# untitled.net
KiCad netlist of a schematic drawn in EAGLE
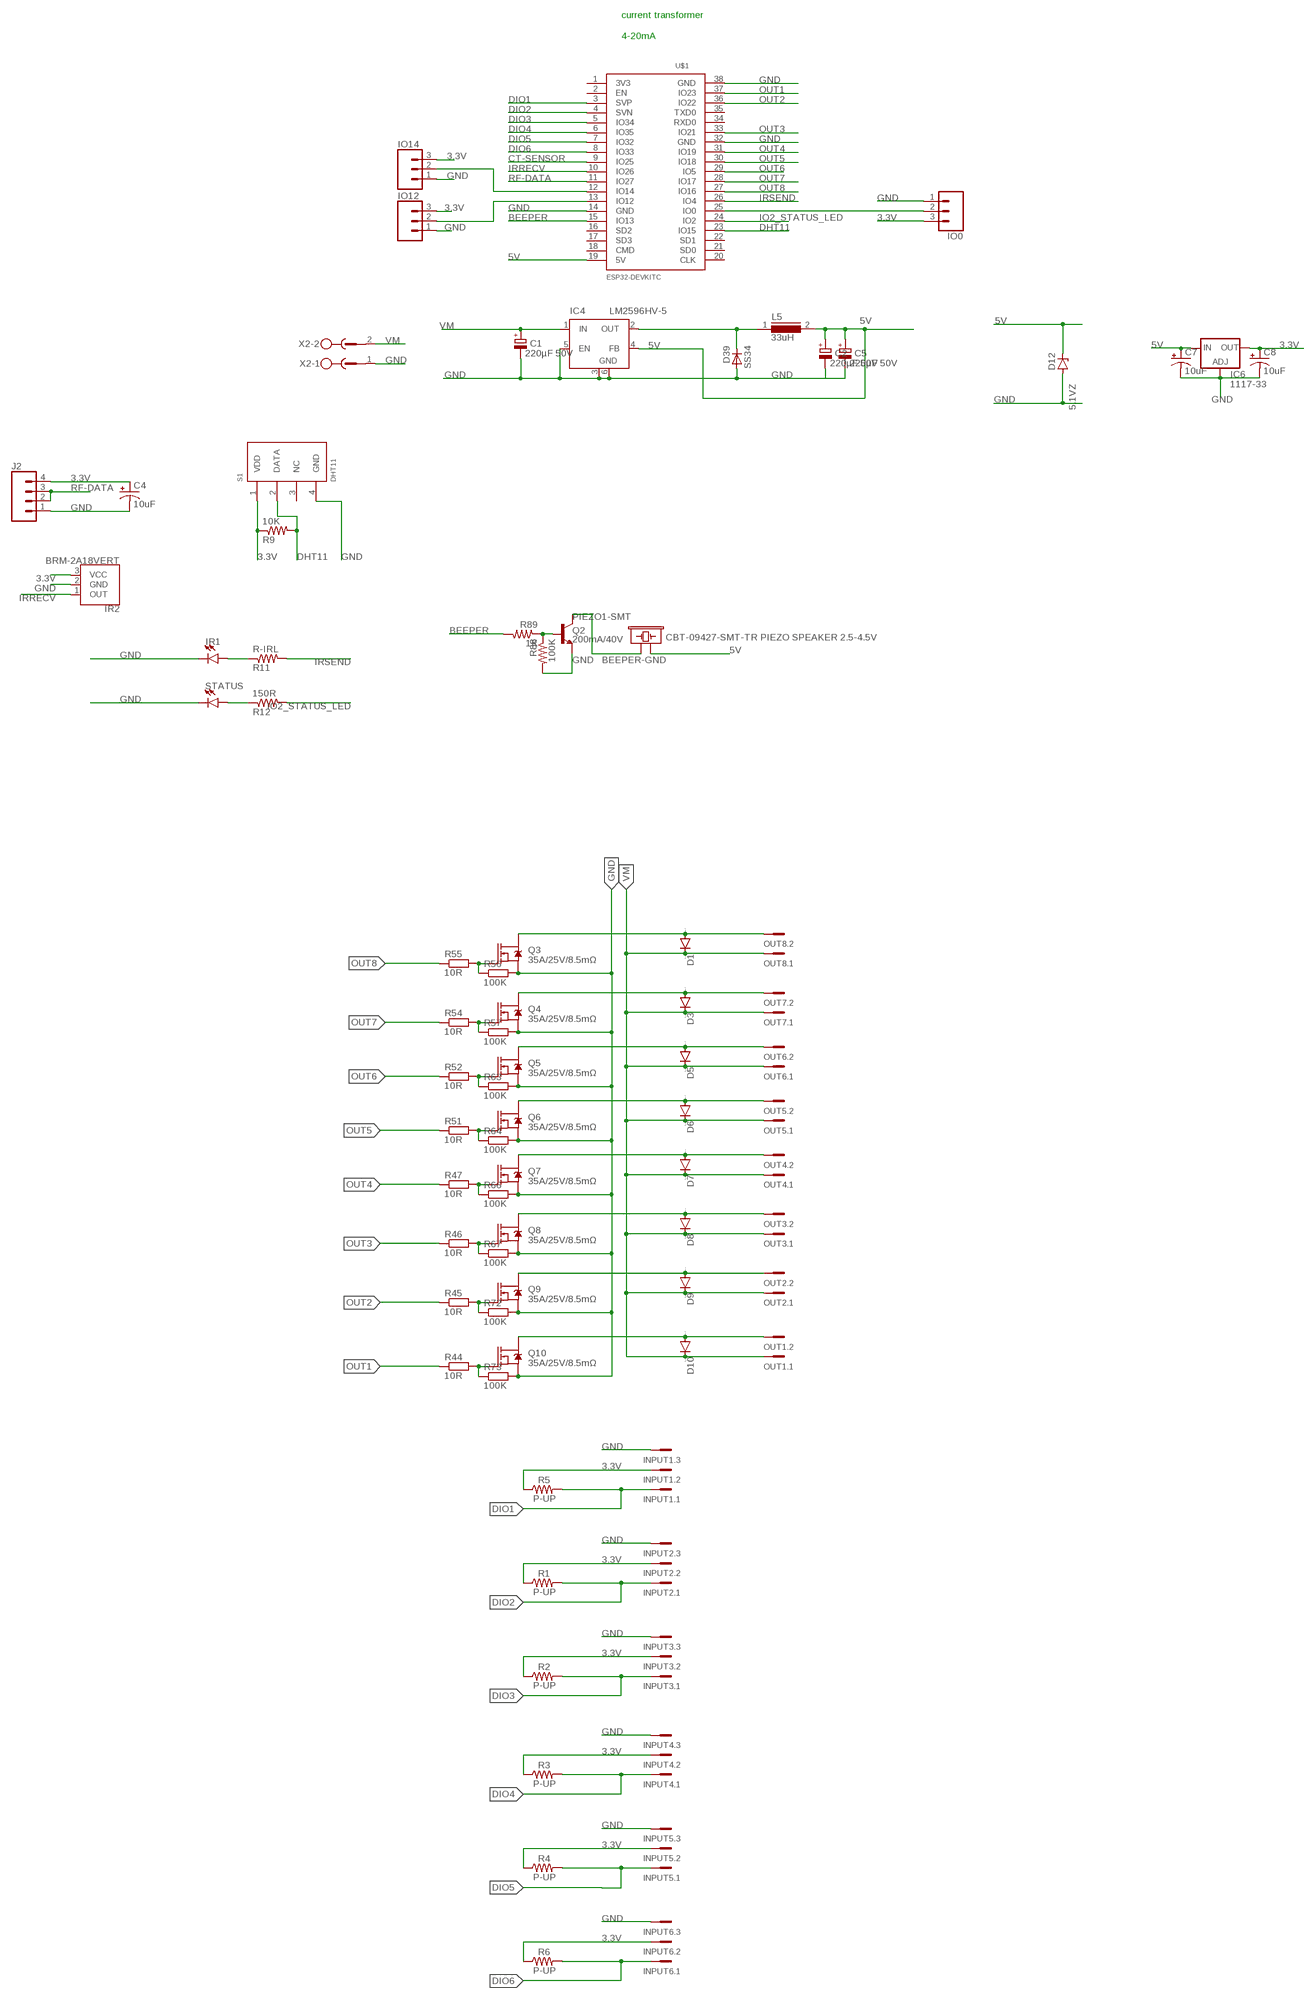
[diagram p0: schematic, sheet 1]

(export (version "E")
  (design (tool "Eeschema 10.0.6"))
  (components
    (comp (ref "C1")
      (value "220µF 50V")
      (footprint "eagle-import:E3,5-8")
      (libsource (lib "eagle-import") (part "CPOL-EUE3.5-8"))
    )
    (comp (ref "C2")
      (value "220µF 50V")
      (footprint "eagle-import:E3,5-8")
      (libsource (lib "eagle-import") (part "CPOL-EUE3.5-8"))
    )
    (comp (ref "C4")
      (value "10uF")
      (footprint "eagle-import:CPOL-RADIAL-10UF-25V")
      (libsource (lib "eagle-import") (part "CAP_POLPTH2"))
    )
    (comp (ref "C5")
      (value "220µF 50V")
      (footprint "eagle-import:E3,5-8")
      (libsource (lib "eagle-import") (part "CPOL-EUE3.5-8"))
    )
    (comp (ref "C7")
      (value "10uF")
      (footprint "eagle-import:CPOL-RADIAL-10UF-25V")
      (libsource (lib "eagle-import") (part "CAP_POLPTH2"))
    )
    (comp (ref "C8")
      (value "10uF")
      (footprint "eagle-import:CPOL-RADIAL-10UF-25V")
      (libsource (lib "eagle-import") (part "CAP_POLPTH2"))
    )
    (comp (ref "D1")
      (value "1N4148DO35-7")
      (footprint "eagle-import:DO35-7")
      (libsource (lib "eagle-import") (part "1N4148DO35-7"))
    )
    (comp (ref "D3")
      (value "1N4148DO35-7")
      (footprint "eagle-import:DO35-7")
      (libsource (lib "eagle-import") (part "1N4148DO35-7"))
    )
    (comp (ref "D5")
      (value "1N4148DO35-7")
      (footprint "eagle-import:DO35-7")
      (libsource (lib "eagle-import") (part "1N4148DO35-7"))
    )
    (comp (ref "D6")
      (value "1N4148DO35-7")
      (footprint "eagle-import:DO35-7")
      (libsource (lib "eagle-import") (part "1N4148DO35-7"))
    )
    (comp (ref "D7")
      (value "1N4148DO35-7")
      (footprint "eagle-import:DO35-7")
      (libsource (lib "eagle-import") (part "1N4148DO35-7"))
    )
    (comp (ref "D8")
      (value "1N4148DO35-7")
      (footprint "eagle-import:DO35-7")
      (libsource (lib "eagle-import") (part "1N4148DO35-7"))
    )
    (comp (ref "D9")
      (value "1N4148DO35-7")
      (footprint "eagle-import:DO35-7")
      (libsource (lib "eagle-import") (part "1N4148DO35-7"))
    )
    (comp (ref "D10")
      (value "1N4148DO35-7")
      (footprint "eagle-import:DO35-7")
      (libsource (lib "eagle-import") (part "1N4148DO35-7"))
    )
    (comp (ref "D12")
      (value "5.1VZ")
      (footprint "eagle-import:SMB")
      (libsource (lib "eagle-import") (part "ZENER-DIODESMB"))
    )
    (comp (ref "D39")
      (value "SS34")
      (footprint "eagle-import:SOD87")
      (libsource (lib "eagle-import") (part "D-SOD-87"))
    )
    (comp (ref "IC4")
      (value "LM2596HV-5")
      (footprint "eagle-import:TO263-5")
      (libsource (lib "eagle-import") (part "LM2596S"))
    )
    (comp (ref "IC6")
      (value "1117-33")
      (footprint "eagle-import:SOT223")
      (libsource (lib "eagle-import") (part "LD117A?S33TR"))
    )
    (comp (ref "INPUT1")
      (value "MCV3")
      (footprint "eagle-import:MCV3")
      (libsource (lib "eagle-import") (part "MCV3"))
    )
    (comp (ref "INPUT2")
      (value "MCV3")
      (footprint "eagle-import:MCV3")
      (libsource (lib "eagle-import") (part "MCV3"))
    )
    (comp (ref "INPUT3")
      (value "MCV3")
      (footprint "eagle-import:MCV3")
      (libsource (lib "eagle-import") (part "MCV3"))
    )
    (comp (ref "INPUT4")
      (value "MCV3")
      (footprint "eagle-import:MCV3")
      (libsource (lib "eagle-import") (part "MCV3"))
    )
    (comp (ref "INPUT5")
      (value "MCV3")
      (footprint "eagle-import:MCV3")
      (libsource (lib "eagle-import") (part "MCV3"))
    )
    (comp (ref "INPUT6")
      (value "MCV3")
      (footprint "eagle-import:MCV3")
      (libsource (lib "eagle-import") (part "MCV3"))
    )
    (comp (ref "IO0")
      (value "CONN_03LOCK")
      (footprint "eagle-import:1X03_LOCK")
      (libsource (lib "eagle-import") (part "CONN_03LOCK"))
    )
    (comp (ref "IO12")
      (value "CONN_03LOCK")
      (footprint "eagle-import:1X03_LOCK")
      (libsource (lib "eagle-import") (part "CONN_03LOCK"))
    )
    (comp (ref "IO14")
      (value "CONN_03LOCK")
      (footprint "eagle-import:1X03_LOCK")
      (libsource (lib "eagle-import") (part "CONN_03LOCK"))
    )
    (comp (ref "IR1")
      (value "LED3MM")
      (footprint "eagle-import:LED_3MM")
      (libsource (lib "eagle-import") (part "LED3MM"))
    )
    (comp (ref "IR2")
      (value "BRM-2A18VERT")
      (footprint "eagle-import:BRM-2508_VERT")
      (libsource (lib "eagle-import") (part "BRM-2A18VERT"))
    )
    (comp (ref "J2")
      (value "CONN_04LOCK")
      (footprint "eagle-import:1X04_LOCK")
      (libsource (lib "eagle-import") (part "CONN_04LOCK"))
    )
    (comp (ref "L5")
      (value "33uH")
      (footprint "eagle-import:DR127")
      (libsource (lib "eagle-import") (part "DR127"))
    )
    (comp (ref "OUT1")
      (value "MCV2")
      (footprint "eagle-import:MCV2")
      (libsource (lib "eagle-import") (part "MCV2"))
    )
    (comp (ref "OUT2")
      (value "MCV2")
      (footprint "eagle-import:MCV2")
      (libsource (lib "eagle-import") (part "MCV2"))
    )
    (comp (ref "OUT3")
      (value "MCV2")
      (footprint "eagle-import:MCV2")
      (libsource (lib "eagle-import") (part "MCV2"))
    )
    (comp (ref "OUT4")
      (value "MCV2")
      (footprint "eagle-import:MCV2")
      (libsource (lib "eagle-import") (part "MCV2"))
    )
    (comp (ref "OUT5")
      (value "MCV2")
      (footprint "eagle-import:MCV2")
      (libsource (lib "eagle-import") (part "MCV2"))
    )
    (comp (ref "OUT6")
      (value "MCV2")
      (footprint "eagle-import:MCV2")
      (libsource (lib "eagle-import") (part "MCV2"))
    )
    (comp (ref "OUT7")
      (value "MCV2")
      (footprint "eagle-import:MCV2")
      (libsource (lib "eagle-import") (part "MCV2"))
    )
    (comp (ref "OUT8")
      (value "MCV2")
      (footprint "eagle-import:MCV2")
      (libsource (lib "eagle-import") (part "MCV2"))
    )
    (comp (ref "PIEZO1-SMT")
      (value "CBT-09427-SMT-TR PIEZO SPEAKER 2.5-4.5V")
      (footprint "eagle-import:BUZZER-12MM")
      (libsource (lib "eagle-import") (part "BUZZER-PTH"))
    )
    (comp (ref "Q2")
      (value "200mA/40V")
      (footprint "eagle-import:TO-92")
      (libsource (lib "eagle-import") (part "TRANS_NPN-2N3904"))
    )
    (comp (ref "Q3")
      (value "35A/25V/8.5mΩ")
      (footprint "eagle-import:DPAK")
      (libsource (lib "eagle-import") (part "MOSFET-NCH-FDD8780"))
    )
    (comp (ref "Q4")
      (value "35A/25V/8.5mΩ")
      (footprint "eagle-import:DPAK")
      (libsource (lib "eagle-import") (part "MOSFET-NCH-FDD8780"))
    )
    (comp (ref "Q5")
      (value "35A/25V/8.5mΩ")
      (footprint "eagle-import:DPAK")
      (libsource (lib "eagle-import") (part "MOSFET-NCH-FDD8780"))
    )
    (comp (ref "Q6")
      (value "35A/25V/8.5mΩ")
      (footprint "eagle-import:DPAK")
      (libsource (lib "eagle-import") (part "MOSFET-NCH-FDD8780"))
    )
    (comp (ref "Q7")
      (value "35A/25V/8.5mΩ")
      (footprint "eagle-import:DPAK")
      (libsource (lib "eagle-import") (part "MOSFET-NCH-FDD8780"))
    )
    (comp (ref "Q8")
      (value "35A/25V/8.5mΩ")
      (footprint "eagle-import:DPAK")
      (libsource (lib "eagle-import") (part "MOSFET-NCH-FDD8780"))
    )
    (comp (ref "Q9")
      (value "35A/25V/8.5mΩ")
      (footprint "eagle-import:DPAK")
      (libsource (lib "eagle-import") (part "MOSFET-NCH-FDD8780"))
    )
    (comp (ref "Q10")
      (value "35A/25V/8.5mΩ")
      (footprint "eagle-import:DPAK")
      (libsource (lib "eagle-import") (part "MOSFET-NCH-FDD8780"))
    )
    (comp (ref "R1")
      (value "P-UP")
      (footprint "eagle-import:0204_7")
      (libsource (lib "eagle-import") (part "resistor_R-US_0204/7"))
    )
    (comp (ref "R2")
      (value "P-UP")
      (footprint "eagle-import:0204_7")
      (libsource (lib "eagle-import") (part "resistor_R-US_0204/7"))
    )
    (comp (ref "R3")
      (value "P-UP")
      (footprint "eagle-import:0204_7")
      (libsource (lib "eagle-import") (part "resistor_R-US_0204/7"))
    )
    (comp (ref "R4")
      (value "P-UP")
      (footprint "eagle-import:0204_7")
      (libsource (lib "eagle-import") (part "resistor_R-US_0204/7"))
    )
    (comp (ref "R5")
      (value "P-UP")
      (footprint "eagle-import:0204_7")
      (libsource (lib "eagle-import") (part "resistor_R-US_0204/7"))
    )
    (comp (ref "R6")
      (value "P-UP")
      (footprint "eagle-import:0204_7")
      (libsource (lib "eagle-import") (part "resistor_R-US_0204/7"))
    )
    (comp (ref "R9")
      (value "10K")
      (footprint "eagle-import:0204_7")
      (libsource (lib "eagle-import") (part "R-US_0204/7"))
    )
    (comp (ref "R11")
      (value "R-IRL")
      (footprint "eagle-import:0204_7")
      (libsource (lib "eagle-import") (part "R-US_0204/7"))
    )
    (comp (ref "R12")
      (value "150R")
      (footprint "eagle-import:0204_7")
      (libsource (lib "eagle-import") (part "R-US_0204/7"))
    )
    (comp (ref "R44")
      (value "10R")
      (footprint "eagle-import:0204_7")
      (libsource (lib "eagle-import") (part "R-EU_0204/7"))
    )
    (comp (ref "R45")
      (value "10R")
      (footprint "eagle-import:0204_7")
      (libsource (lib "eagle-import") (part "R-EU_0204/7"))
    )
    (comp (ref "R46")
      (value "10R")
      (footprint "eagle-import:0204_7")
      (libsource (lib "eagle-import") (part "R-EU_0204/7"))
    )
    (comp (ref "R47")
      (value "10R")
      (footprint "eagle-import:0204_7")
      (libsource (lib "eagle-import") (part "R-EU_0204/7"))
    )
    (comp (ref "R51")
      (value "10R")
      (footprint "eagle-import:0204_7")
      (libsource (lib "eagle-import") (part "R-EU_0204/7"))
    )
    (comp (ref "R52")
      (value "10R")
      (footprint "eagle-import:0204_7")
      (libsource (lib "eagle-import") (part "R-EU_0204/7"))
    )
    (comp (ref "R54")
      (value "10R")
      (footprint "eagle-import:0204_7")
      (libsource (lib "eagle-import") (part "R-EU_0204/7"))
    )
    (comp (ref "R55")
      (value "10R")
      (footprint "eagle-import:0204_7")
      (libsource (lib "eagle-import") (part "R-EU_0204/7"))
    )
    (comp (ref "R56")
      (value "100K")
      (footprint "eagle-import:0204_7")
      (libsource (lib "eagle-import") (part "R-EU_0204/7"))
    )
    (comp (ref "R57")
      (value "100K")
      (footprint "eagle-import:0204_7")
      (libsource (lib "eagle-import") (part "R-EU_0204/7"))
    )
    (comp (ref "R63")
      (value "100K")
      (footprint "eagle-import:0204_7")
      (libsource (lib "eagle-import") (part "R-EU_0204/7"))
    )
    (comp (ref "R64")
      (value "100K")
      (footprint "eagle-import:0204_7")
      (libsource (lib "eagle-import") (part "R-EU_0204/7"))
    )
    (comp (ref "R66")
      (value "100K")
      (footprint "eagle-import:0204_7")
      (libsource (lib "eagle-import") (part "R-EU_0204/7"))
    )
    (comp (ref "R67")
      (value "100K")
      (footprint "eagle-import:0204_7")
      (libsource (lib "eagle-import") (part "R-EU_0204/7"))
    )
    (comp (ref "R72")
      (value "100K")
      (footprint "eagle-import:0204_7")
      (libsource (lib "eagle-import") (part "R-EU_0204/7"))
    )
    (comp (ref "R73")
      (value "100K")
      (footprint "eagle-import:0204_7")
      (libsource (lib "eagle-import") (part "R-EU_0204/7"))
    )
    (comp (ref "R88")
      (value "100K")
      (footprint "eagle-import:0204_7")
      (libsource (lib "eagle-import") (part "adafruit_420_R-US_0204/7"))
    )
    (comp (ref "R89")
      (value "1K")
      (footprint "eagle-import:0204_7")
      (libsource (lib "eagle-import") (part "adafruit_420_R-US_0204/7"))
    )
    (comp (ref "S1")
      (value "DHT11")
      (footprint "eagle-import:DHT11")
      (libsource (lib "eagle-import") (part "DHT11"))
    )
    (comp (ref "STATUS")
      (value "LED3MM")
      (footprint "eagle-import:LED_3MM")
      (libsource (lib "eagle-import") (part "LED3MM"))
    )
    (comp (ref "U$1")
      (value "ESP32NODEMCU")
      (footprint "eagle-import:ESP32NODEMCU")
      (libsource (lib "eagle-import") (part "ESP32NODEMCU"))
    )
    (comp (ref "X2")
      (value "MSTBV2")
      (footprint "eagle-import:MSTBV2")
      (libsource (lib "eagle-import") (part "MSTBV2"))
    )
  )
  (nets
    (net (code "1") (name "/3.3V") (class "Default")
      (node (ref "C4") (pin "1") (pinfunction "+_1") (pintype "passive"))
      (node (ref "C8") (pin "1") (pinfunction "+_1") (pintype "passive"))
      (node (ref "IC6") (pin "4") (pinfunction "OUT_4") (pintype "passive"))
      (node (ref "INPUT1") (pin "2") (pinfunction "SK_2") (pintype "passive"))
      (node (ref "INPUT2") (pin "2") (pinfunction "SK_2") (pintype "passive"))
      (node (ref "INPUT3") (pin "2") (pinfunction "SK_2") (pintype "passive"))
      (node (ref "INPUT4") (pin "2") (pinfunction "SK_2") (pintype "passive"))
      (node (ref "INPUT5") (pin "2") (pinfunction "SK_2") (pintype "passive"))
      (node (ref "INPUT6") (pin "2") (pinfunction "SK_2") (pintype "passive"))
      (node (ref "IO0") (pin "3") (pinfunction "3_3") (pintype "passive"))
      (node (ref "IO12") (pin "3") (pinfunction "3_3") (pintype "passive"))
      (node (ref "IO14") (pin "3") (pinfunction "3_3") (pintype "passive"))
      (node (ref "IR2") (pin "3") (pinfunction "VCC_3") (pintype "bidirectional"))
      (node (ref "J2") (pin "4") (pinfunction "4_4") (pintype "passive"))
      (node (ref "R1") (pin "1") (pinfunction "1_1") (pintype "passive"))
      (node (ref "R2") (pin "1") (pinfunction "1_1") (pintype "passive"))
      (node (ref "R3") (pin "1") (pinfunction "1_1") (pintype "passive"))
      (node (ref "R4") (pin "1") (pinfunction "1_1") (pintype "passive"))
      (node (ref "R5") (pin "1") (pinfunction "1_1") (pintype "passive"))
      (node (ref "R6") (pin "1") (pinfunction "1_1") (pintype "passive"))
      (node (ref "R9") (pin "1") (pinfunction "1_1") (pintype "passive"))
      (node (ref "S1") (pin "1") (pinfunction "VDD_1") (pintype "power_in"))
    )
    (net (code "2") (name "/5V") (class "Default")
      (node (ref "C2") (pin "+") (pinfunction "+_+") (pintype "passive"))
      (node (ref "C5") (pin "+") (pinfunction "+_+") (pintype "passive"))
      (node (ref "C7") (pin "1") (pinfunction "+_1") (pintype "passive"))
      (node (ref "D12") (pin "C") (pinfunction "C_C") (pintype "passive"))
      (node (ref "IC4") (pin "4") (pinfunction "FB_4") (pintype "input"))
      (node (ref "IC6") (pin "3") (pinfunction "IN_3") (pintype "input"))
      (node (ref "L5") (pin "2") (pinfunction "2_2") (pintype "passive"))
      (node (ref "PIEZO1-SMT") (pin "+") (pinfunction "1_+") (pintype "passive"))
      (node (ref "U$1") (pin "19") (pinfunction "5V_19") (pintype "bidirectional"))
    )
    (net (code "3") (name "/BEEPER") (class "Default")
      (node (ref "R89") (pin "2") (pinfunction "2_2") (pintype "passive"))
      (node (ref "U$1") (pin "15") (pinfunction "IO13_15") (pintype "bidirectional"))
    )
    (net (code "4") (name "/BEEPER-GND") (class "Default")
      (node (ref "PIEZO1-SMT") (pin "-") (pinfunction "2_-") (pintype "passive"))
      (node (ref "Q2") (pin "3") (pinfunction "C_3") (pintype "passive"))
    )
    (net (code "5") (name "/CT-SENSOR") (class "Default")
      (node (ref "U$1") (pin "9") (pinfunction "IO25_9") (pintype "bidirectional"))
    )
    (net (code "6") (name "/DHT11") (class "Default")
      (node (ref "R9") (pin "2") (pinfunction "2_2") (pintype "passive"))
      (node (ref "S1") (pin "2") (pinfunction "DATA_2") (pintype "bidirectional"))
      (node (ref "U$1") (pin "23") (pinfunction "IO15_23") (pintype "bidirectional"))
    )
    (net (code "7") (name "/IO2_STATUS_LED") (class "Default")
      (node (ref "R12") (pin "2") (pinfunction "2_2") (pintype "passive"))
      (node (ref "U$1") (pin "24") (pinfunction "IO2_24") (pintype "bidirectional"))
    )
    (net (code "8") (name "/IRRECV") (class "Default")
      (node (ref "IR2") (pin "1") (pinfunction "OUT_1") (pintype "bidirectional"))
      (node (ref "U$1") (pin "10") (pinfunction "IO26_10") (pintype "bidirectional"))
    )
    (net (code "9") (name "/IRSEND") (class "Default")
      (node (ref "R11") (pin "2") (pinfunction "2_2") (pintype "passive"))
      (node (ref "U$1") (pin "26") (pinfunction "IO4_26") (pintype "bidirectional"))
    )
    (net (code "10") (name "/RF-DATA") (class "Default")
      (node (ref "J2") (pin "2") (pinfunction "2_2") (pintype "passive"))
      (node (ref "J2") (pin "3") (pinfunction "3_3") (pintype "passive"))
      (node (ref "U$1") (pin "11") (pinfunction "IO27_11") (pintype "bidirectional"))
    )
    (net (code "11") (name "DIO1") (class "Default")
      (node (ref "INPUT1") (pin "1") (pinfunction "SK_1") (pintype "passive"))
      (node (ref "R5") (pin "2") (pinfunction "2_2") (pintype "passive"))
      (node (ref "U$1") (pin "3") (pinfunction "SVP_3") (pintype "bidirectional"))
    )
    (net (code "12") (name "DIO2") (class "Default")
      (node (ref "INPUT2") (pin "1") (pinfunction "SK_1") (pintype "passive"))
      (node (ref "R1") (pin "2") (pinfunction "2_2") (pintype "passive"))
      (node (ref "U$1") (pin "4") (pinfunction "SVN_4") (pintype "bidirectional"))
    )
    (net (code "13") (name "DIO3") (class "Default")
      (node (ref "INPUT3") (pin "1") (pinfunction "SK_1") (pintype "passive"))
      (node (ref "R2") (pin "2") (pinfunction "2_2") (pintype "passive"))
      (node (ref "U$1") (pin "5") (pinfunction "IO34_5") (pintype "bidirectional"))
    )
    (net (code "14") (name "DIO4") (class "Default")
      (node (ref "INPUT4") (pin "1") (pinfunction "SK_1") (pintype "passive"))
      (node (ref "R3") (pin "2") (pinfunction "2_2") (pintype "passive"))
      (node (ref "U$1") (pin "6") (pinfunction "IO35_6") (pintype "bidirectional"))
    )
    (net (code "15") (name "DIO5") (class "Default")
      (node (ref "INPUT5") (pin "1") (pinfunction "SK_1") (pintype "passive"))
      (node (ref "R4") (pin "2") (pinfunction "2_2") (pintype "passive"))
      (node (ref "U$1") (pin "7") (pinfunction "IO32_7") (pintype "bidirectional"))
    )
    (net (code "16") (name "DIO6") (class "Default")
      (node (ref "INPUT6") (pin "1") (pinfunction "SK_1") (pintype "passive"))
      (node (ref "R6") (pin "2") (pinfunction "2_2") (pintype "passive"))
      (node (ref "U$1") (pin "8") (pinfunction "IO33_8") (pintype "bidirectional"))
    )
    (net (code "17") (name "GND") (class "Default")
      (node (ref "C1") (pin "-") (pinfunction "-_-") (pintype "passive"))
      (node (ref "C2") (pin "-") (pinfunction "-_-") (pintype "passive"))
      (node (ref "C4") (pin "2") (pinfunction "-_2") (pintype "passive"))
      (node (ref "C5") (pin "-") (pinfunction "-_-") (pintype "passive"))
      (node (ref "C7") (pin "2") (pinfunction "-_2") (pintype "passive"))
      (node (ref "C8") (pin "2") (pinfunction "-_2") (pintype "passive"))
      (node (ref "D12") (pin "A") (pinfunction "A_A") (pintype "passive"))
      (node (ref "D39") (pin "2") (pinfunction "A_2") (pintype "passive"))
      (node (ref "IC4") (pin "3") (pinfunction "GND_3") (pintype "power_in"))
      (node (ref "IC4") (pin "5") (pinfunction "EN_5") (pintype "input"))
      (node (ref "IC4") (pin "6") (pinfunction "GND_6") (pintype "power_in"))
      (node (ref "IC6") (pin "1") (pinfunction "ADJ_1") (pintype "input"))
      (node (ref "INPUT1") (pin "3") (pinfunction "SK_3") (pintype "passive"))
      (node (ref "INPUT2") (pin "3") (pinfunction "SK_3") (pintype "passive"))
      (node (ref "INPUT3") (pin "3") (pinfunction "SK_3") (pintype "passive"))
      (node (ref "INPUT4") (pin "3") (pinfunction "SK_3") (pintype "passive"))
      (node (ref "INPUT5") (pin "3") (pinfunction "SK_3") (pintype "passive"))
      (node (ref "INPUT6") (pin "3") (pinfunction "SK_3") (pintype "passive"))
      (node (ref "IO0") (pin "1") (pinfunction "1_1") (pintype "passive"))
      (node (ref "IO12") (pin "1") (pinfunction "1_1") (pintype "passive"))
      (node (ref "IO14") (pin "1") (pinfunction "1_1") (pintype "passive"))
      (node (ref "IR1") (pin "K") (pinfunction "C_K") (pintype "passive"))
      (node (ref "IR2") (pin "2") (pinfunction "GND_2") (pintype "bidirectional"))
      (node (ref "J2") (pin "1") (pinfunction "1_1") (pintype "passive"))
      (node (ref "Q10") (pin "3") (pinfunction "S_3") (pintype "bidirectional"))
      (node (ref "Q2") (pin "1") (pinfunction "E_1") (pintype "passive"))
      (node (ref "Q3") (pin "3") (pinfunction "S_3") (pintype "bidirectional"))
      (node (ref "Q4") (pin "3") (pinfunction "S_3") (pintype "bidirectional"))
      (node (ref "Q5") (pin "3") (pinfunction "S_3") (pintype "bidirectional"))
      (node (ref "Q6") (pin "3") (pinfunction "S_3") (pintype "bidirectional"))
      (node (ref "Q7") (pin "3") (pinfunction "S_3") (pintype "bidirectional"))
      (node (ref "Q8") (pin "3") (pinfunction "S_3") (pintype "bidirectional"))
      (node (ref "Q9") (pin "3") (pinfunction "S_3") (pintype "bidirectional"))
      (node (ref "R56") (pin "2") (pinfunction "2_2") (pintype "passive"))
      (node (ref "R57") (pin "2") (pinfunction "2_2") (pintype "passive"))
      (node (ref "R63") (pin "2") (pinfunction "2_2") (pintype "passive"))
      (node (ref "R64") (pin "2") (pinfunction "2_2") (pintype "passive"))
      (node (ref "R66") (pin "2") (pinfunction "2_2") (pintype "passive"))
      (node (ref "R67") (pin "2") (pinfunction "2_2") (pintype "passive"))
      (node (ref "R72") (pin "2") (pinfunction "2_2") (pintype "passive"))
      (node (ref "R73") (pin "2") (pinfunction "2_2") (pintype "passive"))
      (node (ref "R88") (pin "2") (pinfunction "2_2") (pintype "passive"))
      (node (ref "S1") (pin "4") (pinfunction "GND_4") (pintype "power_in"))
      (node (ref "STATUS") (pin "K") (pinfunction "C_K") (pintype "passive"))
      (node (ref "U$1") (pin "14") (pinfunction "GND_14") (pintype "bidirectional"))
      (node (ref "U$1") (pin "32") (pinfunction "GND_32") (pintype "bidirectional"))
      (node (ref "U$1") (pin "38") (pinfunction "GND_38") (pintype "bidirectional"))
      (node (ref "X2") (pin "1") (pinfunction "SK_1") (pintype "passive"))
    )
    (net (code "18") (name "Net-(D39-C)") (class "Default")
      (node (ref "D39") (pin "1") (pinfunction "C_1") (pintype "passive"))
      (node (ref "IC4") (pin "2") (pinfunction "OUT_2") (pintype "output"))
      (node (ref "L5") (pin "1") (pinfunction "1_1") (pintype "passive"))
    )
    (net (code "19") (name "Net-(IR1-PadA)") (class "Default")
      (node (ref "IR1") (pin "A") (pinfunction "A_A") (pintype "passive"))
      (node (ref "R11") (pin "1") (pinfunction "1_1") (pintype "passive"))
    )
    (net (code "20") (name "Net-(OUT1B-SK)") (class "Default")
      (node (ref "D10") (pin "A") (pinfunction "A_A") (pintype "passive"))
      (node (ref "OUT1") (pin "2") (pinfunction "SK_2") (pintype "passive"))
      (node (ref "Q10") (pin "4") (pinfunction "D_4") (pintype "bidirectional"))
    )
    (net (code "21") (name "Net-(OUT2B-SK)") (class "Default")
      (node (ref "D9") (pin "A") (pinfunction "A_A") (pintype "passive"))
      (node (ref "OUT2") (pin "2") (pinfunction "SK_2") (pintype "passive"))
      (node (ref "Q9") (pin "4") (pinfunction "D_4") (pintype "bidirectional"))
    )
    (net (code "22") (name "Net-(OUT3B-SK)") (class "Default")
      (node (ref "D8") (pin "A") (pinfunction "A_A") (pintype "passive"))
      (node (ref "OUT3") (pin "2") (pinfunction "SK_2") (pintype "passive"))
      (node (ref "Q8") (pin "4") (pinfunction "D_4") (pintype "bidirectional"))
    )
    (net (code "23") (name "Net-(OUT4B-SK)") (class "Default")
      (node (ref "D7") (pin "A") (pinfunction "A_A") (pintype "passive"))
      (node (ref "OUT4") (pin "2") (pinfunction "SK_2") (pintype "passive"))
      (node (ref "Q7") (pin "4") (pinfunction "D_4") (pintype "bidirectional"))
    )
    (net (code "24") (name "Net-(OUT5B-SK)") (class "Default")
      (node (ref "D6") (pin "A") (pinfunction "A_A") (pintype "passive"))
      (node (ref "OUT5") (pin "2") (pinfunction "SK_2") (pintype "passive"))
      (node (ref "Q6") (pin "4") (pinfunction "D_4") (pintype "bidirectional"))
    )
    (net (code "25") (name "Net-(OUT6B-SK)") (class "Default")
      (node (ref "D5") (pin "A") (pinfunction "A_A") (pintype "passive"))
      (node (ref "OUT6") (pin "2") (pinfunction "SK_2") (pintype "passive"))
      (node (ref "Q5") (pin "4") (pinfunction "D_4") (pintype "bidirectional"))
    )
    (net (code "26") (name "Net-(OUT7B-SK)") (class "Default")
      (node (ref "D3") (pin "A") (pinfunction "A_A") (pintype "passive"))
      (node (ref "OUT7") (pin "2") (pinfunction "SK_2") (pintype "passive"))
      (node (ref "Q4") (pin "4") (pinfunction "D_4") (pintype "bidirectional"))
    )
    (net (code "27") (name "Net-(OUT8B-SK)") (class "Default")
      (node (ref "D1") (pin "A") (pinfunction "A_A") (pintype "passive"))
      (node (ref "OUT8") (pin "2") (pinfunction "SK_2") (pintype "passive"))
      (node (ref "Q3") (pin "4") (pinfunction "D_4") (pintype "bidirectional"))
    )
    (net (code "28") (name "Net-(Q2-B)") (class "Default")
      (node (ref "Q2") (pin "2") (pinfunction "B_2") (pintype "passive"))
      (node (ref "R88") (pin "1") (pinfunction "1_1") (pintype "passive"))
      (node (ref "R89") (pin "1") (pinfunction "1_1") (pintype "passive"))
    )
    (net (code "29") (name "Net-(Q3-G)") (class "Default")
      (node (ref "Q3") (pin "1") (pinfunction "G_1") (pintype "bidirectional"))
      (node (ref "R55") (pin "2") (pinfunction "2_2") (pintype "passive"))
      (node (ref "R56") (pin "1") (pinfunction "1_1") (pintype "passive"))
    )
    (net (code "30") (name "Net-(Q4-G)") (class "Default")
      (node (ref "Q4") (pin "1") (pinfunction "G_1") (pintype "bidirectional"))
      (node (ref "R54") (pin "2") (pinfunction "2_2") (pintype "passive"))
      (node (ref "R57") (pin "1") (pinfunction "1_1") (pintype "passive"))
    )
    (net (code "31") (name "Net-(Q5-G)") (class "Default")
      (node (ref "Q5") (pin "1") (pinfunction "G_1") (pintype "bidirectional"))
      (node (ref "R52") (pin "2") (pinfunction "2_2") (pintype "passive"))
      (node (ref "R63") (pin "1") (pinfunction "1_1") (pintype "passive"))
    )
    (net (code "32") (name "Net-(Q6-G)") (class "Default")
      (node (ref "Q6") (pin "1") (pinfunction "G_1") (pintype "bidirectional"))
      (node (ref "R51") (pin "2") (pinfunction "2_2") (pintype "passive"))
      (node (ref "R64") (pin "1") (pinfunction "1_1") (pintype "passive"))
    )
    (net (code "33") (name "Net-(Q7-G)") (class "Default")
      (node (ref "Q7") (pin "1") (pinfunction "G_1") (pintype "bidirectional"))
      (node (ref "R47") (pin "2") (pinfunction "2_2") (pintype "passive"))
      (node (ref "R66") (pin "1") (pinfunction "1_1") (pintype "passive"))
    )
    (net (code "34") (name "Net-(Q8-G)") (class "Default")
      (node (ref "Q8") (pin "1") (pinfunction "G_1") (pintype "bidirectional"))
      (node (ref "R46") (pin "2") (pinfunction "2_2") (pintype "passive"))
      (node (ref "R67") (pin "1") (pinfunction "1_1") (pintype "passive"))
    )
    (net (code "35") (name "Net-(Q9-G)") (class "Default")
      (node (ref "Q9") (pin "1") (pinfunction "G_1") (pintype "bidirectional"))
      (node (ref "R45") (pin "2") (pinfunction "2_2") (pintype "passive"))
      (node (ref "R72") (pin "1") (pinfunction "1_1") (pintype "passive"))
    )
    (net (code "36") (name "Net-(Q10-G)") (class "Default")
      (node (ref "Q10") (pin "1") (pinfunction "G_1") (pintype "bidirectional"))
      (node (ref "R44") (pin "2") (pinfunction "2_2") (pintype "passive"))
      (node (ref "R73") (pin "1") (pinfunction "1_1") (pintype "passive"))
    )
    (net (code "37") (name "Net-(R12-Pad1)") (class "Default")
      (node (ref "R12") (pin "1") (pinfunction "1_1") (pintype "passive"))
      (node (ref "STATUS") (pin "A") (pinfunction "A_A") (pintype "passive"))
    )
    (net (code "38") (name "Net-(U$1-IO0)") (class "Default")
      (node (ref "IO0") (pin "2") (pinfunction "2_2") (pintype "passive"))
      (node (ref "U$1") (pin "25") (pinfunction "IO0_25") (pintype "bidirectional"))
    )
    (net (code "39") (name "Net-(U$1-IO12)") (class "Default")
      (node (ref "IO12") (pin "2") (pinfunction "2_2") (pintype "passive"))
      (node (ref "U$1") (pin "13") (pinfunction "IO12_13") (pintype "bidirectional"))
    )
    (net (code "40") (name "Net-(U$1-IO14)") (class "Default")
      (node (ref "IO14") (pin "2") (pinfunction "2_2") (pintype "passive"))
      (node (ref "U$1") (pin "12") (pinfunction "IO14_12") (pintype "bidirectional"))
    )
    (net (code "41") (name "OUT1") (class "Default")
      (node (ref "R44") (pin "1") (pinfunction "1_1") (pintype "passive"))
      (node (ref "U$1") (pin "37") (pinfunction "IO23_37") (pintype "bidirectional"))
    )
    (net (code "42") (name "OUT2") (class "Default")
      (node (ref "R45") (pin "1") (pinfunction "1_1") (pintype "passive"))
      (node (ref "U$1") (pin "36") (pinfunction "IO22_36") (pintype "bidirectional"))
    )
    (net (code "43") (name "OUT3") (class "Default")
      (node (ref "R46") (pin "1") (pinfunction "1_1") (pintype "passive"))
      (node (ref "U$1") (pin "33") (pinfunction "IO21_33") (pintype "bidirectional"))
    )
    (net (code "44") (name "OUT4") (class "Default")
      (node (ref "R47") (pin "1") (pinfunction "1_1") (pintype "passive"))
      (node (ref "U$1") (pin "31") (pinfunction "IO19_31") (pintype "bidirectional"))
    )
    (net (code "45") (name "OUT5") (class "Default")
      (node (ref "R51") (pin "1") (pinfunction "1_1") (pintype "passive"))
      (node (ref "U$1") (pin "30") (pinfunction "IO18_30") (pintype "bidirectional"))
    )
    (net (code "46") (name "OUT6") (class "Default")
      (node (ref "R52") (pin "1") (pinfunction "1_1") (pintype "passive"))
      (node (ref "U$1") (pin "29") (pinfunction "IO5_29") (pintype "bidirectional"))
    )
    (net (code "47") (name "OUT7") (class "Default")
      (node (ref "R54") (pin "1") (pinfunction "1_1") (pintype "passive"))
      (node (ref "U$1") (pin "28") (pinfunction "IO17_28") (pintype "bidirectional"))
    )
    (net (code "48") (name "OUT8") (class "Default")
      (node (ref "R55") (pin "1") (pinfunction "1_1") (pintype "passive"))
      (node (ref "U$1") (pin "27") (pinfunction "IO16_27") (pintype "bidirectional"))
    )
    (net (code "49") (name "VM") (class "Default")
      (node (ref "C1") (pin "+") (pinfunction "+_+") (pintype "passive"))
      (node (ref "D1") (pin "C") (pinfunction "C_C") (pintype "passive"))
      (node (ref "D10") (pin "C") (pinfunction "C_C") (pintype "passive"))
      (node (ref "D3") (pin "C") (pinfunction "C_C") (pintype "passive"))
      (node (ref "D5") (pin "C") (pinfunction "C_C") (pintype "passive"))
      (node (ref "D6") (pin "C") (pinfunction "C_C") (pintype "passive"))
      (node (ref "D7") (pin "C") (pinfunction "C_C") (pintype "passive"))
      (node (ref "D8") (pin "C") (pinfunction "C_C") (pintype "passive"))
      (node (ref "D9") (pin "C") (pinfunction "C_C") (pintype "passive"))
      (node (ref "IC4") (pin "1") (pinfunction "IN_1") (pintype "input"))
      (node (ref "OUT1") (pin "1") (pinfunction "SK_1") (pintype "passive"))
      (node (ref "OUT2") (pin "1") (pinfunction "SK_1") (pintype "passive"))
      (node (ref "OUT3") (pin "1") (pinfunction "SK_1") (pintype "passive"))
      (node (ref "OUT4") (pin "1") (pinfunction "SK_1") (pintype "passive"))
      (node (ref "OUT5") (pin "1") (pinfunction "SK_1") (pintype "passive"))
      (node (ref "OUT6") (pin "1") (pinfunction "SK_1") (pintype "passive"))
      (node (ref "OUT7") (pin "1") (pinfunction "SK_1") (pintype "passive"))
      (node (ref "OUT8") (pin "1") (pinfunction "SK_1") (pintype "passive"))
      (node (ref "X2") (pin "2") (pinfunction "SK_2") (pintype "passive"))
    )
    (net (code "50") (name "unconnected-(S1-NC-Pad3)") (class "Default")
      (node (ref "S1") (pin "3") (pinfunction "NC_3") (pintype "bidirectional"))
    )
    (net (code "51") (name "unconnected-(U$1-3V3-Pad1)") (class "Default")
      (node (ref "U$1") (pin "1") (pinfunction "3V3_1") (pintype "bidirectional"))
    )
    (net (code "52") (name "unconnected-(U$1-CLK-Pad20)") (class "Default")
      (node (ref "U$1") (pin "20") (pinfunction "CLK_20") (pintype "bidirectional"))
    )
    (net (code "53") (name "unconnected-(U$1-CMD-Pad18)") (class "Default")
      (node (ref "U$1") (pin "18") (pinfunction "CMD_18") (pintype "bidirectional"))
    )
    (net (code "54") (name "unconnected-(U$1-EN-Pad2)") (class "Default")
      (node (ref "U$1") (pin "2") (pinfunction "EN_2") (pintype "bidirectional"))
    )
    (net (code "55") (name "unconnected-(U$1-RXD0-Pad34)") (class "Default")
      (node (ref "U$1") (pin "34") (pinfunction "RXD0_34") (pintype "bidirectional"))
    )
    (net (code "56") (name "unconnected-(U$1-SD0-Pad21)") (class "Default")
      (node (ref "U$1") (pin "21") (pinfunction "SD0_21") (pintype "bidirectional"))
    )
    (net (code "57") (name "unconnected-(U$1-SD1-Pad22)") (class "Default")
      (node (ref "U$1") (pin "22") (pinfunction "SD1_22") (pintype "bidirectional"))
    )
    (net (code "58") (name "unconnected-(U$1-SD2-Pad16)") (class "Default")
      (node (ref "U$1") (pin "16") (pinfunction "SD2_16") (pintype "bidirectional"))
    )
    (net (code "59") (name "unconnected-(U$1-SD3-Pad17)") (class "Default")
      (node (ref "U$1") (pin "17") (pinfunction "SD3_17") (pintype "bidirectional"))
    )
    (net (code "60") (name "unconnected-(U$1-TXD0-Pad35)") (class "Default")
      (node (ref "U$1") (pin "35") (pinfunction "TXD0_35") (pintype "bidirectional"))
    )
  )
)
